# connectors.net
KiCad netlist of a schematic drawn in Altium Designer
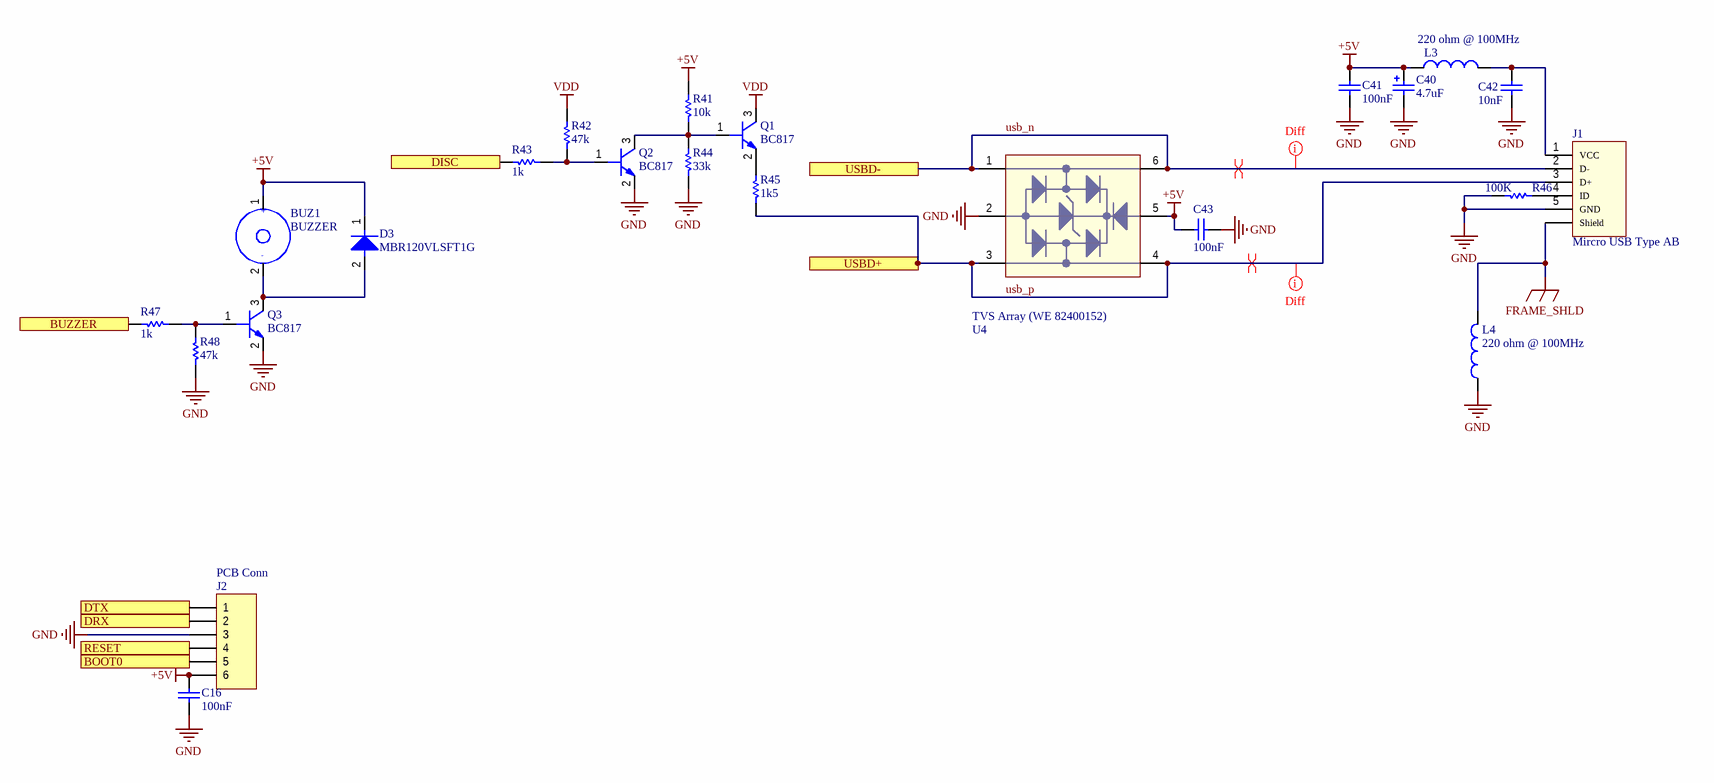
[diagram p0: connectors.SchDoc]

(export (version "E")
  (design (tool "Eeschema 10.0.6"))
  (components
    (comp (ref "BUZ1")
      (value "BUZZER")
      (footprint "BUZZER_7.5x7.5_SMD")
      (libsource (lib "develer_library") (part "BUZZER"))
    )
    (comp (ref "C16")
      (value "100nF")
      (footprint "0603_[1608]")
      (description "Ceramic X7R 50V")
      (fields (field (name "PUBLISHER") "Altium Limited"))
      (libsource (lib "Miscellaneous Devices") (part "Cap"))
    )
    (comp (ref "C40")
      (value "4.7uF")
      (footprint "1206_[3216]")
      (description "Ceramic X7R 16V")
      (fields (field (name "PUBLISHER") "Altium Limited"))
      (libsource (lib "DEVELER_Library") (part "Cap Pol1"))
    )
    (comp (ref "C41")
      (value "100nF")
      (footprint "0603_[1608]")
      (description "Ceramic X7R 50V")
      (fields (field (name "PUBLISHER") "Altium Limited"))
      (libsource (lib "DEVELER_Library") (part "Cap"))
    )
    (comp (ref "C42")
      (value "10nF")
      (footprint "0603_[1608]")
      (description "Ceramic X7R 50V")
      (fields (field (name "PUBLISHER") "Altium Limited"))
      (libsource (lib "DEVELER_Library") (part "Cap"))
    )
    (comp (ref "C43")
      (value "100nF")
      (footprint "0603_[1608]")
      (description "Ceramic X7R 50V")
      (fields (field (name "PUBLISHER") "Altium Limited"))
      (libsource (lib "Miscellaneous Devices") (part "Cap"))
    )
    (comp (ref "D3")
      (value "MBR120VLSFT1G")
      (footprint "SOD-123")
      (description "Diode Schottky  low Vf, If 1A (PMEG3010ER; MBRX120LF)")
      (libsource (lib "DEVELER_Library") (part "Diode"))
    )
    (comp (ref "J1")
      (value "Mircro USB Type AB")
      (footprint "USB_MICRO_AB_SMD")
      (description "Micro USB 2.0 Type AB Horizontal WR-COM")
      (fields (field (name "PART NUMBER") "629105150921") (field (name "PUBLISHER") "Wurth Elektronik"))
      (libsource (lib "develer_library") (part "USB_MICRO_TypeAB"))
    )
    (comp (ref "J2")
      (value "PCB Conn")
      (footprint "HEADER_1X6_2.54MM_ANGLED_THD")
      (description "Header, 6-Pin")
      (fields (field (name "PUBLISHER") "Altium Limited"))
      (libsource (lib "Miscellaneous Connectors") (part "Header 6"))
    )
    (comp (ref "L3")
      (value "220 ohm @ 100MHz")
      (footprint "0805_[2012]")
      (description "WE 742792022")
      (libsource (lib "DEVELER_Library") (part "Inductor"))
    )
    (comp (ref "L4")
      (value "220 ohm @ 100MHz")
      (footprint "0805_[2012]")
      (description "WE 742792022")
      (libsource (lib "DEVELER_Library") (part "Inductor"))
    )
    (comp (ref "Q1")
      (value "BC817")
      (footprint "SOT-23")
      (description "BJT NPN")
      (libsource (lib "develer_library") (part "BC817"))
    )
    (comp (ref "Q2")
      (value "BC817")
      (footprint "SOT-23")
      (description "BJT NPN")
      (libsource (lib "develer_library") (part "BC817"))
    )
    (comp (ref "Q3")
      (value "BC817")
      (footprint "SOT-23")
      (description "BJT NPN")
      (libsource (lib "develer_library") (part "BC817"))
    )
    (comp (ref "R41")
      (value "10k")
      (footprint "0603_[1608]")
      (description "Resistor")
      (fields (field (name "PUBLISHER") "Altium Limited"))
      (libsource (lib "DEVELER_Library") (part "Res1"))
    )
    (comp (ref "R42")
      (value "47k")
      (footprint "0603_[1608]")
      (description "Resistor")
      (fields (field (name "PUBLISHER") "Altium Limited"))
      (libsource (lib "DEVELER_Library") (part "Res1"))
    )
    (comp (ref "R43")
      (value "1k")
      (footprint "0603_[1608]")
      (description "Resistor")
      (fields (field (name "PUBLISHER") "Altium Limited"))
      (libsource (lib "DEVELER_Library") (part "Res1"))
    )
    (comp (ref "R44")
      (value "33k")
      (footprint "0603_[1608]")
      (description "Resistor")
      (fields (field (name "PUBLISHER") "Altium Limited"))
      (libsource (lib "DEVELER_Library") (part "Res1"))
    )
    (comp (ref "R45")
      (value "1k5")
      (footprint "0603_[1608]")
      (description "Resistor")
      (fields (field (name "PUBLISHER") "Altium Limited"))
      (libsource (lib "DEVELER_Library") (part "Res1"))
    )
    (comp (ref "R46")
      (value "100K")
      (footprint "0603_[1608]")
      (description "Resistor")
      (libsource (lib "Miscellaneous Devices") (part "Res1"))
    )
    (comp (ref "R47")
      (value "1k")
      (footprint "0603_[1608]")
      (description "Resistor")
      (fields (field (name "PUBLISHER") "Altium Limited"))
      (libsource (lib "DEVELER_Library") (part "Res1"))
    )
    (comp (ref "R48")
      (value "47k")
      (footprint "0603_[1608]")
      (description "Resistor")
      (fields (field (name "PUBLISHER") "Altium Limited"))
      (libsource (lib "DEVELER_Library") (part "Res1"))
    )
    (comp (ref "U4")
      (value "TVS Array (WE 82400152)")
      (footprint "SOT-563")
      (libsource (lib "DEVELER_Library") (part "TVS_Diode_Array"))
    )
  )
  (nets
    (net (code "1") (name "+5V") (class "Default")
      (node (ref "BUZ1") (pin "1") (pinfunction "1_1") (pintype "bidirectional"))
      (node (ref "C16") (pin "2") (pinfunction "2_2") (pintype "passive"))
      (node (ref "C40") (pin "1") (pinfunction "1_1") (pintype "passive"))
      (node (ref "C41") (pin "1") (pinfunction "1_1") (pintype "passive"))
      (node (ref "C43") (pin "2") (pinfunction "2_2") (pintype "passive"))
      (node (ref "D3") (pin "1") (pinfunction "K_1") (pintype "passive"))
      (node (ref "J2") (pin "6") (pinfunction "6_6") (pintype "passive"))
      (node (ref "L3") (pin "1") (pinfunction "1_1") (pintype "passive"))
      (node (ref "R41") (pin "1") (pinfunction "1_1") (pintype "passive"))
      (node (ref "U4") (pin "5") (pinfunction "5_5") (pintype "passive"))
    )
    (net (code "2") (name "/BOOT0") (class "Default")
      (node (ref "J2") (pin "5") (pinfunction "5_5") (pintype "passive"))
    )
    (net (code "3") (name "/BUZZER") (class "Default")
      (node (ref "R47") (pin "2") (pinfunction "2_2") (pintype "passive"))
    )
    (net (code "4") (name "/DISC") (class "Default")
      (node (ref "R43") (pin "2") (pinfunction "2_2") (pintype "passive"))
    )
    (net (code "5") (name "/DRX") (class "Default")
      (node (ref "J2") (pin "2") (pinfunction "2_2") (pintype "passive"))
    )
    (net (code "6") (name "/DTX") (class "Default")
      (node (ref "J2") (pin "1") (pinfunction "1_1") (pintype "passive"))
    )
    (net (code "7") (name "/RESET") (class "Default")
      (node (ref "J2") (pin "4") (pinfunction "4_4") (pintype "passive"))
    )
    (net (code "8") (name "/usb_n") (class "Default")
      (node (ref "J1") (pin "2") (pinfunction "D-_2") (pintype "passive"))
      (node (ref "U4") (pin "1") (pinfunction "1_1") (pintype "passive"))
      (node (ref "U4") (pin "6") (pinfunction "6_6") (pintype "passive"))
    )
    (net (code "9") (name "/usb_p") (class "Default")
      (node (ref "J1") (pin "3") (pinfunction "D+_3") (pintype "passive"))
      (node (ref "R45") (pin "2") (pinfunction "2_2") (pintype "passive"))
      (node (ref "U4") (pin "3") (pinfunction "3_3") (pintype "passive"))
      (node (ref "U4") (pin "4") (pinfunction "4_4") (pintype "passive"))
    )
    (net (code "10") (name "FRAME_SHLD") (class "Default")
      (node (ref "J1") (pin "Shell") (pinfunction "Shield_Shell") (pintype "passive"))
      (node (ref "L4") (pin "2") (pinfunction "2_2") (pintype "passive"))
    )
    (net (code "11") (name "GND") (class "Default")
      (node (ref "C16") (pin "1") (pinfunction "1_1") (pintype "passive"))
      (node (ref "C40") (pin "2") (pinfunction "2_2") (pintype "passive"))
      (node (ref "C41") (pin "2") (pinfunction "2_2") (pintype "passive"))
      (node (ref "C42") (pin "2") (pinfunction "2_2") (pintype "passive"))
      (node (ref "C43") (pin "1") (pinfunction "1_1") (pintype "passive"))
      (node (ref "J1") (pin "5") (pinfunction "GND_5") (pintype "passive"))
      (node (ref "J2") (pin "3") (pinfunction "3_3") (pintype "passive"))
      (node (ref "L4") (pin "1") (pinfunction "1_1") (pintype "passive"))
      (node (ref "Q2") (pin "2") (pinfunction "E_2") (pintype "passive"))
      (node (ref "Q3") (pin "2") (pinfunction "E_2") (pintype "passive"))
      (node (ref "R44") (pin "2") (pinfunction "2_2") (pintype "passive"))
      (node (ref "R46") (pin "2") (pinfunction "2_2") (pintype "passive"))
      (node (ref "R48") (pin "2") (pinfunction "2_2") (pintype "passive"))
      (node (ref "U4") (pin "2") (pinfunction "2_2") (pintype "passive"))
    )
    (net (code "12") (name "Net-(D3-A)") (class "Default")
      (node (ref "BUZ1") (pin "2") (pinfunction "2_2") (pintype "bidirectional"))
      (node (ref "D3") (pin "2") (pinfunction "A_2") (pintype "passive"))
      (node (ref "Q3") (pin "3") (pinfunction "C_3") (pintype "passive"))
    )
    (net (code "13") (name "Net-(J1-ID)") (class "Default")
      (node (ref "J1") (pin "4") (pinfunction "ID_4") (pintype "passive"))
      (node (ref "R46") (pin "1") (pinfunction "1_1") (pintype "passive"))
    )
    (net (code "14") (name "Net-(J1-VCC)") (class "Default")
      (node (ref "C42") (pin "1") (pinfunction "1_1") (pintype "passive"))
      (node (ref "J1") (pin "1") (pinfunction "VCC_1") (pintype "passive"))
      (node (ref "L3") (pin "2") (pinfunction "2_2") (pintype "passive"))
    )
    (net (code "15") (name "Net-(Q1-B)") (class "Default")
      (node (ref "Q1") (pin "1") (pinfunction "B_1") (pintype "passive"))
      (node (ref "Q2") (pin "3") (pinfunction "C_3") (pintype "passive"))
      (node (ref "R41") (pin "2") (pinfunction "2_2") (pintype "passive"))
      (node (ref "R44") (pin "1") (pinfunction "1_1") (pintype "passive"))
    )
    (net (code "16") (name "Net-(Q1-E)") (class "Default")
      (node (ref "Q1") (pin "2") (pinfunction "E_2") (pintype "passive"))
      (node (ref "R45") (pin "1") (pinfunction "1_1") (pintype "passive"))
    )
    (net (code "17") (name "Net-(Q2-B)") (class "Default")
      (node (ref "Q2") (pin "1") (pinfunction "B_1") (pintype "passive"))
      (node (ref "R42") (pin "2") (pinfunction "2_2") (pintype "passive"))
      (node (ref "R43") (pin "1") (pinfunction "1_1") (pintype "passive"))
    )
    (net (code "18") (name "Net-(Q3-B)") (class "Default")
      (node (ref "Q3") (pin "1") (pinfunction "B_1") (pintype "passive"))
      (node (ref "R47") (pin "1") (pinfunction "1_1") (pintype "passive"))
      (node (ref "R48") (pin "1") (pinfunction "1_1") (pintype "passive"))
    )
    (net (code "19") (name "VDD") (class "Default")
      (node (ref "Q1") (pin "3") (pinfunction "C_3") (pintype "passive"))
      (node (ref "R42") (pin "1") (pinfunction "1_1") (pintype "passive"))
    )
  )
)
